# balloon-atmega-v04.net
KiCad netlist of a schematic drawn in EAGLE
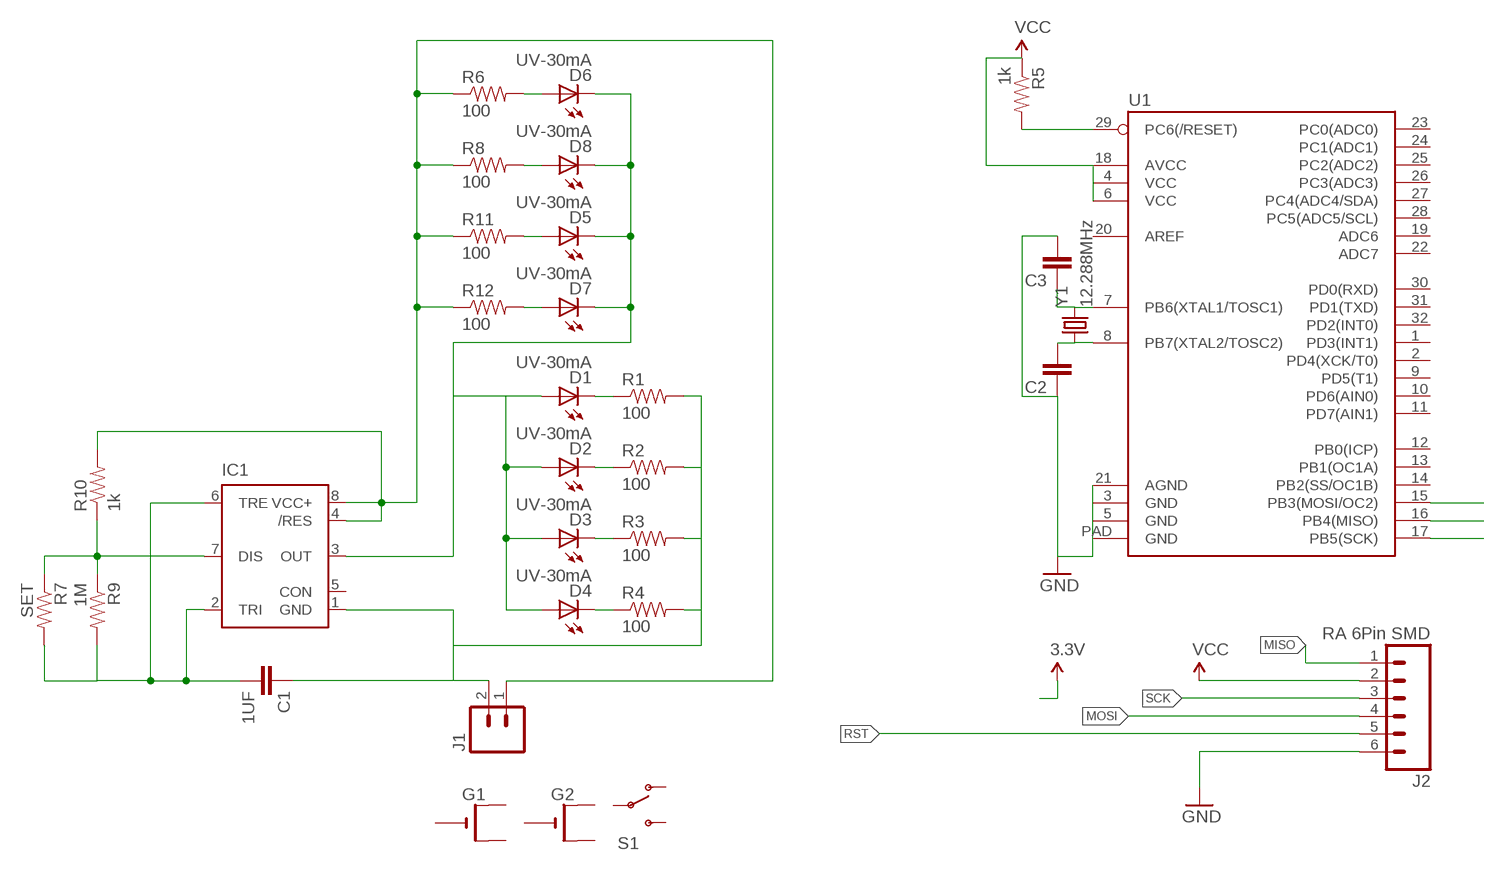
[diagram p0: schematic, sheet 1]

(export (version "E")
  (design (tool "Eeschema 10.0.6"))
  (components
    (comp (ref "C1")
      (value "1UF")
      (footprint "eagle-import:0603-CAP")
      (libsource (lib "eagle-import") (part "CAP0603-CAP"))
    )
    (comp (ref "C2")
      (value "CAP0603-CAP")
      (footprint "eagle-import:0603-CAP")
      (libsource (lib "eagle-import") (part "SparkFun-Passives_CAP0603-CAP"))
    )
    (comp (ref "C3")
      (value "CAP0603-CAP")
      (footprint "eagle-import:0603-CAP")
      (libsource (lib "eagle-import") (part "SparkFun-Passives_CAP0603-CAP"))
    )
    (comp (ref "D1")
      (value "UV-30mA")
      (footprint "eagle-import:CHIPLED_0603")
      (libsource (lib "eagle-import") (part "LEDCHIPLED_0603"))
    )
    (comp (ref "D2")
      (value "UV-30mA")
      (footprint "eagle-import:CHIPLED_0603")
      (libsource (lib "eagle-import") (part "LEDCHIPLED_0603"))
    )
    (comp (ref "D3")
      (value "UV-30mA")
      (footprint "eagle-import:CHIPLED_0603")
      (libsource (lib "eagle-import") (part "LEDCHIPLED_0603"))
    )
    (comp (ref "D4")
      (value "UV-30mA")
      (footprint "eagle-import:CHIPLED_0603")
      (libsource (lib "eagle-import") (part "LEDCHIPLED_0603"))
    )
    (comp (ref "D5")
      (value "UV-30mA")
      (footprint "eagle-import:CHIPLED_0603")
      (libsource (lib "eagle-import") (part "LEDCHIPLED_0603"))
    )
    (comp (ref "D6")
      (value "UV-30mA")
      (footprint "eagle-import:CHIPLED_0603")
      (libsource (lib "eagle-import") (part "LEDCHIPLED_0603"))
    )
    (comp (ref "D7")
      (value "UV-30mA")
      (footprint "eagle-import:CHIPLED_0603")
      (libsource (lib "eagle-import") (part "LEDCHIPLED_0603"))
    )
    (comp (ref "D8")
      (value "UV-30mA")
      (footprint "eagle-import:CHIPLED_0603")
      (libsource (lib "eagle-import") (part "LEDCHIPLED_0603"))
    )
    (comp (ref "G1")
      (value "CR2032SMT")
      (footprint "eagle-import:CR2032-SMD")
      (libsource (lib "eagle-import") (part "CR2032SMT"))
    )
    (comp (ref "G2")
      (value "CR2032SMT")
      (footprint "eagle-import:CR2032-SMD")
      (libsource (lib "eagle-import") (part "CR2032SMT"))
    )
    (comp (ref "IC1")
      (value "NE555D")
      (footprint "eagle-import:SO08")
      (libsource (lib "eagle-import") (part "NE555D"))
    )
    (comp (ref "J1")
      (value "M02PTH3")
      (footprint "eagle-import:1X02_LONGPADS")
      (libsource (lib "eagle-import") (part "M02PTH3"))
    )
    (comp (ref "J2")
      (value "RA 6Pin SMD")
      (footprint "eagle-import:1X06_SMD_MALE")
      (libsource (lib "eagle-import") (part "M06SMD_MALE"))
    )
    (comp (ref "R1")
      (value "100")
      (footprint "eagle-import:0603-RES")
      (libsource (lib "eagle-import") (part "RESISTOR0603-RES"))
    )
    (comp (ref "R2")
      (value "100")
      (footprint "eagle-import:0603-RES")
      (libsource (lib "eagle-import") (part "RESISTOR0603-RES"))
    )
    (comp (ref "R3")
      (value "100")
      (footprint "eagle-import:0603-RES")
      (libsource (lib "eagle-import") (part "RESISTOR0603-RES"))
    )
    (comp (ref "R4")
      (value "100")
      (footprint "eagle-import:0603-RES")
      (libsource (lib "eagle-import") (part "RESISTOR0603-RES"))
    )
    (comp (ref "R5")
      (value "1k")
      (footprint "eagle-import:0603-RES")
      (libsource (lib "eagle-import") (part "RESISTOR0603-RES"))
    )
    (comp (ref "R6")
      (value "100")
      (footprint "eagle-import:0603-RES")
      (libsource (lib "eagle-import") (part "RESISTOR0603-RES"))
    )
    (comp (ref "R7")
      (value "SET")
      (footprint "eagle-import:0603-RES")
      (libsource (lib "eagle-import") (part "RESISTOR0603"))
    )
    (comp (ref "R8")
      (value "100")
      (footprint "eagle-import:0603-RES")
      (libsource (lib "eagle-import") (part "RESISTOR0603-RES"))
    )
    (comp (ref "R9")
      (value "1M")
      (footprint "eagle-import:0603-RES")
      (libsource (lib "eagle-import") (part "RESISTOR0603-RES"))
    )
    (comp (ref "R10")
      (value "1k")
      (footprint "eagle-import:0603-RES")
      (libsource (lib "eagle-import") (part "RESISTOR0603-RES"))
    )
    (comp (ref "R11")
      (value "100")
      (footprint "eagle-import:0603-RES")
      (libsource (lib "eagle-import") (part "RESISTOR0603-RES"))
    )
    (comp (ref "R12")
      (value "100")
      (footprint "eagle-import:0603-RES")
      (libsource (lib "eagle-import") (part "RESISTOR0603-RES"))
    )
    (comp (ref "S1")
      (value "SWITCH-SPDT-SMD-A")
      (footprint "eagle-import:SWITCH-SPST-SMD-A")
      (libsource (lib "eagle-import") (part "SWITCH-SPDT-SMD-A"))
    )
    (comp (ref "U1")
      (value "ATMEGA328P_MLFMLF32")
      (footprint "eagle-import:MLF32-PAD")
      (libsource (lib "eagle-import") (part "ATMEGA328P_MLFMLF32"))
    )
    (comp (ref "Y1")
      (value "12.288MHz")
      (footprint "eagle-import:CRYSTAL-SMD-5X3")
      (libsource (lib "eagle-import") (part "CRYSTALCRYSTAL-SMD-5X3-12.288MHZ"))
    )
  )
  (nets
    (net (code "2") (name "GND") (class "Default")
      (node (ref "C1") (pin "1") (pinfunction "1_1") (pintype "passive"))
      (node (ref "C2") (pin "1") (pinfunction "1_1") (pintype "passive"))
      (node (ref "C3") (pin "2") (pinfunction "2_2") (pintype "passive"))
      (node (ref "IC1") (pin "1") (pinfunction "GND_1") (pintype "power_in"))
      (node (ref "J1") (pin "2") (pinfunction "2_2") (pintype "passive"))
      (node (ref "J2") (pin "6") (pinfunction "6_6") (pintype "passive"))
      (node (ref "R1") (pin "2") (pinfunction "2_2") (pintype "passive"))
      (node (ref "R2") (pin "2") (pinfunction "2_2") (pintype "passive"))
      (node (ref "R3") (pin "2") (pinfunction "2_2") (pintype "passive"))
      (node (ref "R4") (pin "2") (pinfunction "2_2") (pintype "passive"))
      (node (ref "U1") (pin "21") (pinfunction "AGND_21") (pintype "bidirectional"))
      (node (ref "U1") (pin "3") (pinfunction "GND_3") (pintype "bidirectional"))
      (node (ref "U1") (pin "5") (pinfunction "GND_5") (pintype "bidirectional"))
      (node (ref "U1") (pin "PAD") (pinfunction "GND_PAD") (pintype "bidirectional"))
    )
    (net (code "3") (name "MISO") (class "Default")
      (node (ref "J2") (pin "1") (pinfunction "1_1") (pintype "passive"))
      (node (ref "U1") (pin "16") (pinfunction "PB4(MISO)_16") (pintype "bidirectional"))
    )
    (net (code "4") (name "MOSI") (class "Default")
      (node (ref "J2") (pin "4") (pinfunction "4_4") (pintype "passive"))
      (node (ref "U1") (pin "15") (pinfunction "PB3(MOSI/OC2)_15") (pintype "bidirectional"))
    )
    (net (code "5") (name "Net-(D1-PadC)") (class "Default")
      (node (ref "D1") (pin "C") (pinfunction "C_C") (pintype "passive"))
      (node (ref "R1") (pin "1") (pinfunction "1_1") (pintype "passive"))
    )
    (net (code "6") (name "Net-(D2-PadC)") (class "Default")
      (node (ref "D2") (pin "C") (pinfunction "C_C") (pintype "passive"))
      (node (ref "R2") (pin "1") (pinfunction "1_1") (pintype "passive"))
    )
    (net (code "7") (name "Net-(D3-PadC)") (class "Default")
      (node (ref "D3") (pin "C") (pinfunction "C_C") (pintype "passive"))
      (node (ref "R3") (pin "1") (pinfunction "1_1") (pintype "passive"))
    )
    (net (code "8") (name "Net-(D4-PadC)") (class "Default")
      (node (ref "D4") (pin "C") (pinfunction "C_C") (pintype "passive"))
      (node (ref "R4") (pin "1") (pinfunction "1_1") (pintype "passive"))
    )
    (net (code "9") (name "Net-(D5-PadA)") (class "Default")
      (node (ref "D5") (pin "A") (pinfunction "A_A") (pintype "passive"))
      (node (ref "R11") (pin "2") (pinfunction "2_2") (pintype "passive"))
    )
    (net (code "10") (name "Net-(D6-PadA)") (class "Default")
      (node (ref "D6") (pin "A") (pinfunction "A_A") (pintype "passive"))
      (node (ref "R6") (pin "2") (pinfunction "2_2") (pintype "passive"))
    )
    (net (code "11") (name "Net-(D7-PadA)") (class "Default")
      (node (ref "D7") (pin "A") (pinfunction "A_A") (pintype "passive"))
      (node (ref "R12") (pin "2") (pinfunction "2_2") (pintype "passive"))
    )
    (net (code "12") (name "Net-(D8-PadA)") (class "Default")
      (node (ref "D8") (pin "A") (pinfunction "A_A") (pintype "passive"))
      (node (ref "R8") (pin "2") (pinfunction "2_2") (pintype "passive"))
    )
    (net (code "13") (name "Net-(IC1-DIS)") (class "Default")
      (node (ref "IC1") (pin "7") (pinfunction "DIS_7") (pintype "input"))
      (node (ref "R10") (pin "1") (pinfunction "1_1") (pintype "passive"))
      (node (ref "R7") (pin "1") (pinfunction "1_1") (pintype "passive"))
      (node (ref "R9") (pin "1") (pinfunction "1_1") (pintype "passive"))
    )
    (net (code "14") (name "Net-(IC1-OUT)") (class "Default")
      (node (ref "D1") (pin "A") (pinfunction "A_A") (pintype "passive"))
      (node (ref "D2") (pin "A") (pinfunction "A_A") (pintype "passive"))
      (node (ref "D3") (pin "A") (pinfunction "A_A") (pintype "passive"))
      (node (ref "D4") (pin "A") (pinfunction "A_A") (pintype "passive"))
      (node (ref "D5") (pin "C") (pinfunction "C_C") (pintype "passive"))
      (node (ref "D6") (pin "C") (pinfunction "C_C") (pintype "passive"))
      (node (ref "D7") (pin "C") (pinfunction "C_C") (pintype "passive"))
      (node (ref "D8") (pin "C") (pinfunction "C_C") (pintype "passive"))
      (node (ref "IC1") (pin "3") (pinfunction "OUT_3") (pintype "output"))
    )
    (net (code "15") (name "Net-(IC1-TRE)") (class "Default")
      (node (ref "C1") (pin "2") (pinfunction "2_2") (pintype "passive"))
      (node (ref "IC1") (pin "2") (pinfunction "TRI_2") (pintype "input"))
      (node (ref "IC1") (pin "6") (pinfunction "TRE_6") (pintype "input"))
      (node (ref "R7") (pin "2") (pinfunction "2_2") (pintype "passive"))
      (node (ref "R9") (pin "2") (pinfunction "2_2") (pintype "passive"))
    )
    (net (code "16") (name "Net-(U1-PB6(XTAL1{slash}TOSC1))") (class "Default")
      (node (ref "C3") (pin "1") (pinfunction "1_1") (pintype "passive"))
      (node (ref "U1") (pin "7") (pinfunction "PB6(XTAL1/TOSC1)_7") (pintype "bidirectional"))
      (node (ref "Y1") (pin "3") (pinfunction "2_3") (pintype "passive"))
    )
    (net (code "17") (name "Net-(U1-PB7(XTAL2{slash}TOSC2))") (class "Default")
      (node (ref "C2") (pin "2") (pinfunction "2_2") (pintype "passive"))
      (node (ref "U1") (pin "8") (pinfunction "PB7(XTAL2/TOSC2)_8") (pintype "bidirectional"))
      (node (ref "Y1") (pin "1") (pinfunction "1_1") (pintype "passive"))
    )
    (net (code "18") (name "RST") (class "Default")
      (node (ref "J2") (pin "5") (pinfunction "5_5") (pintype "passive"))
      (node (ref "R5") (pin "2") (pinfunction "2_2") (pintype "passive"))
      (node (ref "U1") (pin "29") (pinfunction "PC6(/RESET)_29") (pintype "bidirectional"))
    )
    (net (code "19") (name "SCK") (class "Default")
      (node (ref "J2") (pin "3") (pinfunction "3_3") (pintype "passive"))
      (node (ref "U1") (pin "17") (pinfunction "PB5(SCK)_17") (pintype "bidirectional"))
    )
    (net (code "20") (name "VCC") (class "Default")
      (node (ref "IC1") (pin "4") (pinfunction "/RES_4") (pintype "input"))
      (node (ref "IC1") (pin "8") (pinfunction "VCC+_8") (pintype "power_in"))
      (node (ref "J1") (pin "1") (pinfunction "1_1") (pintype "passive"))
      (node (ref "J2") (pin "2") (pinfunction "2_2") (pintype "passive"))
      (node (ref "R10") (pin "2") (pinfunction "2_2") (pintype "passive"))
      (node (ref "R11") (pin "1") (pinfunction "1_1") (pintype "passive"))
      (node (ref "R12") (pin "1") (pinfunction "1_1") (pintype "passive"))
      (node (ref "R5") (pin "1") (pinfunction "1_1") (pintype "passive"))
      (node (ref "R6") (pin "1") (pinfunction "1_1") (pintype "passive"))
      (node (ref "R8") (pin "1") (pinfunction "1_1") (pintype "passive"))
      (node (ref "U1") (pin "18") (pinfunction "AVCC_18") (pintype "bidirectional"))
      (node (ref "U1") (pin "4") (pinfunction "VCC_4") (pintype "bidirectional"))
      (node (ref "U1") (pin "6") (pinfunction "VCC_6") (pintype "bidirectional"))
    )
    (net (code "21") (name "unconnected-(G1-+-Pad+$1)") (class "Default")
      (node (ref "G1") (pin "+$1") (pinfunction "+_+$1") (pintype "passive"))
    )
    (net (code "22") (name "unconnected-(G1-+1-Pad+$2)") (class "Default")
      (node (ref "G1") (pin "+$2") (pinfunction "+1_+$2") (pintype "passive"))
    )
    (net (code "23") (name "unconnected-(G1-Pad-)") (class "Default")
      (node (ref "G1") (pin "-") (pinfunction "-_-") (pintype "passive"))
    )
    (net (code "24") (name "unconnected-(G2-+-Pad+$1)") (class "Default")
      (node (ref "G2") (pin "+$1") (pinfunction "+_+$1") (pintype "passive"))
    )
    (net (code "25") (name "unconnected-(G2-+1-Pad+$2)") (class "Default")
      (node (ref "G2") (pin "+$2") (pinfunction "+1_+$2") (pintype "passive"))
    )
    (net (code "26") (name "unconnected-(G2-Pad-)") (class "Default")
      (node (ref "G2") (pin "-") (pinfunction "-_-") (pintype "passive"))
    )
    (net (code "27") (name "unconnected-(IC1-CON-Pad5)") (class "Default")
      (node (ref "IC1") (pin "5") (pinfunction "CON_5") (pintype "input"))
    )
    (net (code "28") (name "unconnected-(S1-O-Pad1)") (class "Default")
      (node (ref "S1") (pin "1") (pinfunction "O_1") (pintype "passive"))
    )
    (net (code "29") (name "unconnected-(S1-P-Pad2)") (class "Default")
      (node (ref "S1") (pin "2") (pinfunction "P_2") (pintype "passive"))
    )
    (net (code "30") (name "unconnected-(S1-S-Pad3)") (class "Default")
      (node (ref "S1") (pin "3") (pinfunction "S_3") (pintype "passive"))
    )
    (net (code "31") (name "unconnected-(U1-ADC6-Pad19)") (class "Default")
      (node (ref "U1") (pin "19") (pinfunction "ADC6_19") (pintype "bidirectional"))
    )
    (net (code "32") (name "unconnected-(U1-ADC7-Pad22)") (class "Default")
      (node (ref "U1") (pin "22") (pinfunction "ADC7_22") (pintype "bidirectional"))
    )
    (net (code "33") (name "unconnected-(U1-AREF-Pad20)") (class "Default")
      (node (ref "U1") (pin "20") (pinfunction "AREF_20") (pintype "bidirectional"))
    )
    (net (code "34") (name "unconnected-(U1-PB0(ICP)-Pad12)") (class "Default")
      (node (ref "U1") (pin "12") (pinfunction "PB0(ICP)_12") (pintype "bidirectional"))
    )
    (net (code "35") (name "unconnected-(U1-PB1(OC1A)-Pad13)") (class "Default")
      (node (ref "U1") (pin "13") (pinfunction "PB1(OC1A)_13") (pintype "bidirectional"))
    )
    (net (code "36") (name "unconnected-(U1-PB2(SS{slash}OC1B)-Pad14)") (class "Default")
      (node (ref "U1") (pin "14") (pinfunction "PB2(SS/OC1B)_14") (pintype "bidirectional"))
    )
    (net (code "37") (name "unconnected-(U1-PC0(ADC0)-Pad23)") (class "Default")
      (node (ref "U1") (pin "23") (pinfunction "PC0(ADC0)_23") (pintype "bidirectional"))
    )
    (net (code "38") (name "unconnected-(U1-PC1(ADC1)-Pad24)") (class "Default")
      (node (ref "U1") (pin "24") (pinfunction "PC1(ADC1)_24") (pintype "bidirectional"))
    )
    (net (code "39") (name "unconnected-(U1-PC2(ADC2)-Pad25)") (class "Default")
      (node (ref "U1") (pin "25") (pinfunction "PC2(ADC2)_25") (pintype "bidirectional"))
    )
    (net (code "40") (name "unconnected-(U1-PC3(ADC3)-Pad26)") (class "Default")
      (node (ref "U1") (pin "26") (pinfunction "PC3(ADC3)_26") (pintype "bidirectional"))
    )
    (net (code "41") (name "unconnected-(U1-PC4(ADC4{slash}SDA)-Pad27)") (class "Default")
      (node (ref "U1") (pin "27") (pinfunction "PC4(ADC4/SDA)_27") (pintype "bidirectional"))
    )
    (net (code "42") (name "unconnected-(U1-PC5(ADC5{slash}SCL)-Pad28)") (class "Default")
      (node (ref "U1") (pin "28") (pinfunction "PC5(ADC5/SCL)_28") (pintype "bidirectional"))
    )
    (net (code "43") (name "unconnected-(U1-PD0(RXD)-Pad30)") (class "Default")
      (node (ref "U1") (pin "30") (pinfunction "PD0(RXD)_30") (pintype "bidirectional"))
    )
    (net (code "44") (name "unconnected-(U1-PD1(TXD)-Pad31)") (class "Default")
      (node (ref "U1") (pin "31") (pinfunction "PD1(TXD)_31") (pintype "bidirectional"))
    )
    (net (code "45") (name "unconnected-(U1-PD2(INT0)-Pad32)") (class "Default")
      (node (ref "U1") (pin "32") (pinfunction "PD2(INT0)_32") (pintype "bidirectional"))
    )
    (net (code "46") (name "unconnected-(U1-PD3(INT1)-Pad1)") (class "Default")
      (node (ref "U1") (pin "1") (pinfunction "PD3(INT1)_1") (pintype "bidirectional"))
    )
    (net (code "47") (name "unconnected-(U1-PD4(XCK{slash}T0)-Pad2)") (class "Default")
      (node (ref "U1") (pin "2") (pinfunction "PD4(XCK/T0)_2") (pintype "bidirectional"))
    )
    (net (code "48") (name "unconnected-(U1-PD5(T1)-Pad9)") (class "Default")
      (node (ref "U1") (pin "9") (pinfunction "PD5(T1)_9") (pintype "bidirectional"))
    )
    (net (code "49") (name "unconnected-(U1-PD6(AIN0)-Pad10)") (class "Default")
      (node (ref "U1") (pin "10") (pinfunction "PD6(AIN0)_10") (pintype "bidirectional"))
    )
    (net (code "50") (name "unconnected-(U1-PD7(AIN1)-Pad11)") (class "Default")
      (node (ref "U1") (pin "11") (pinfunction "PD7(AIN1)_11") (pintype "bidirectional"))
    )
  )
)
